# LEDMatrixLearningBadge.net
KiCad netlist of a schematic drawn in EAGLE
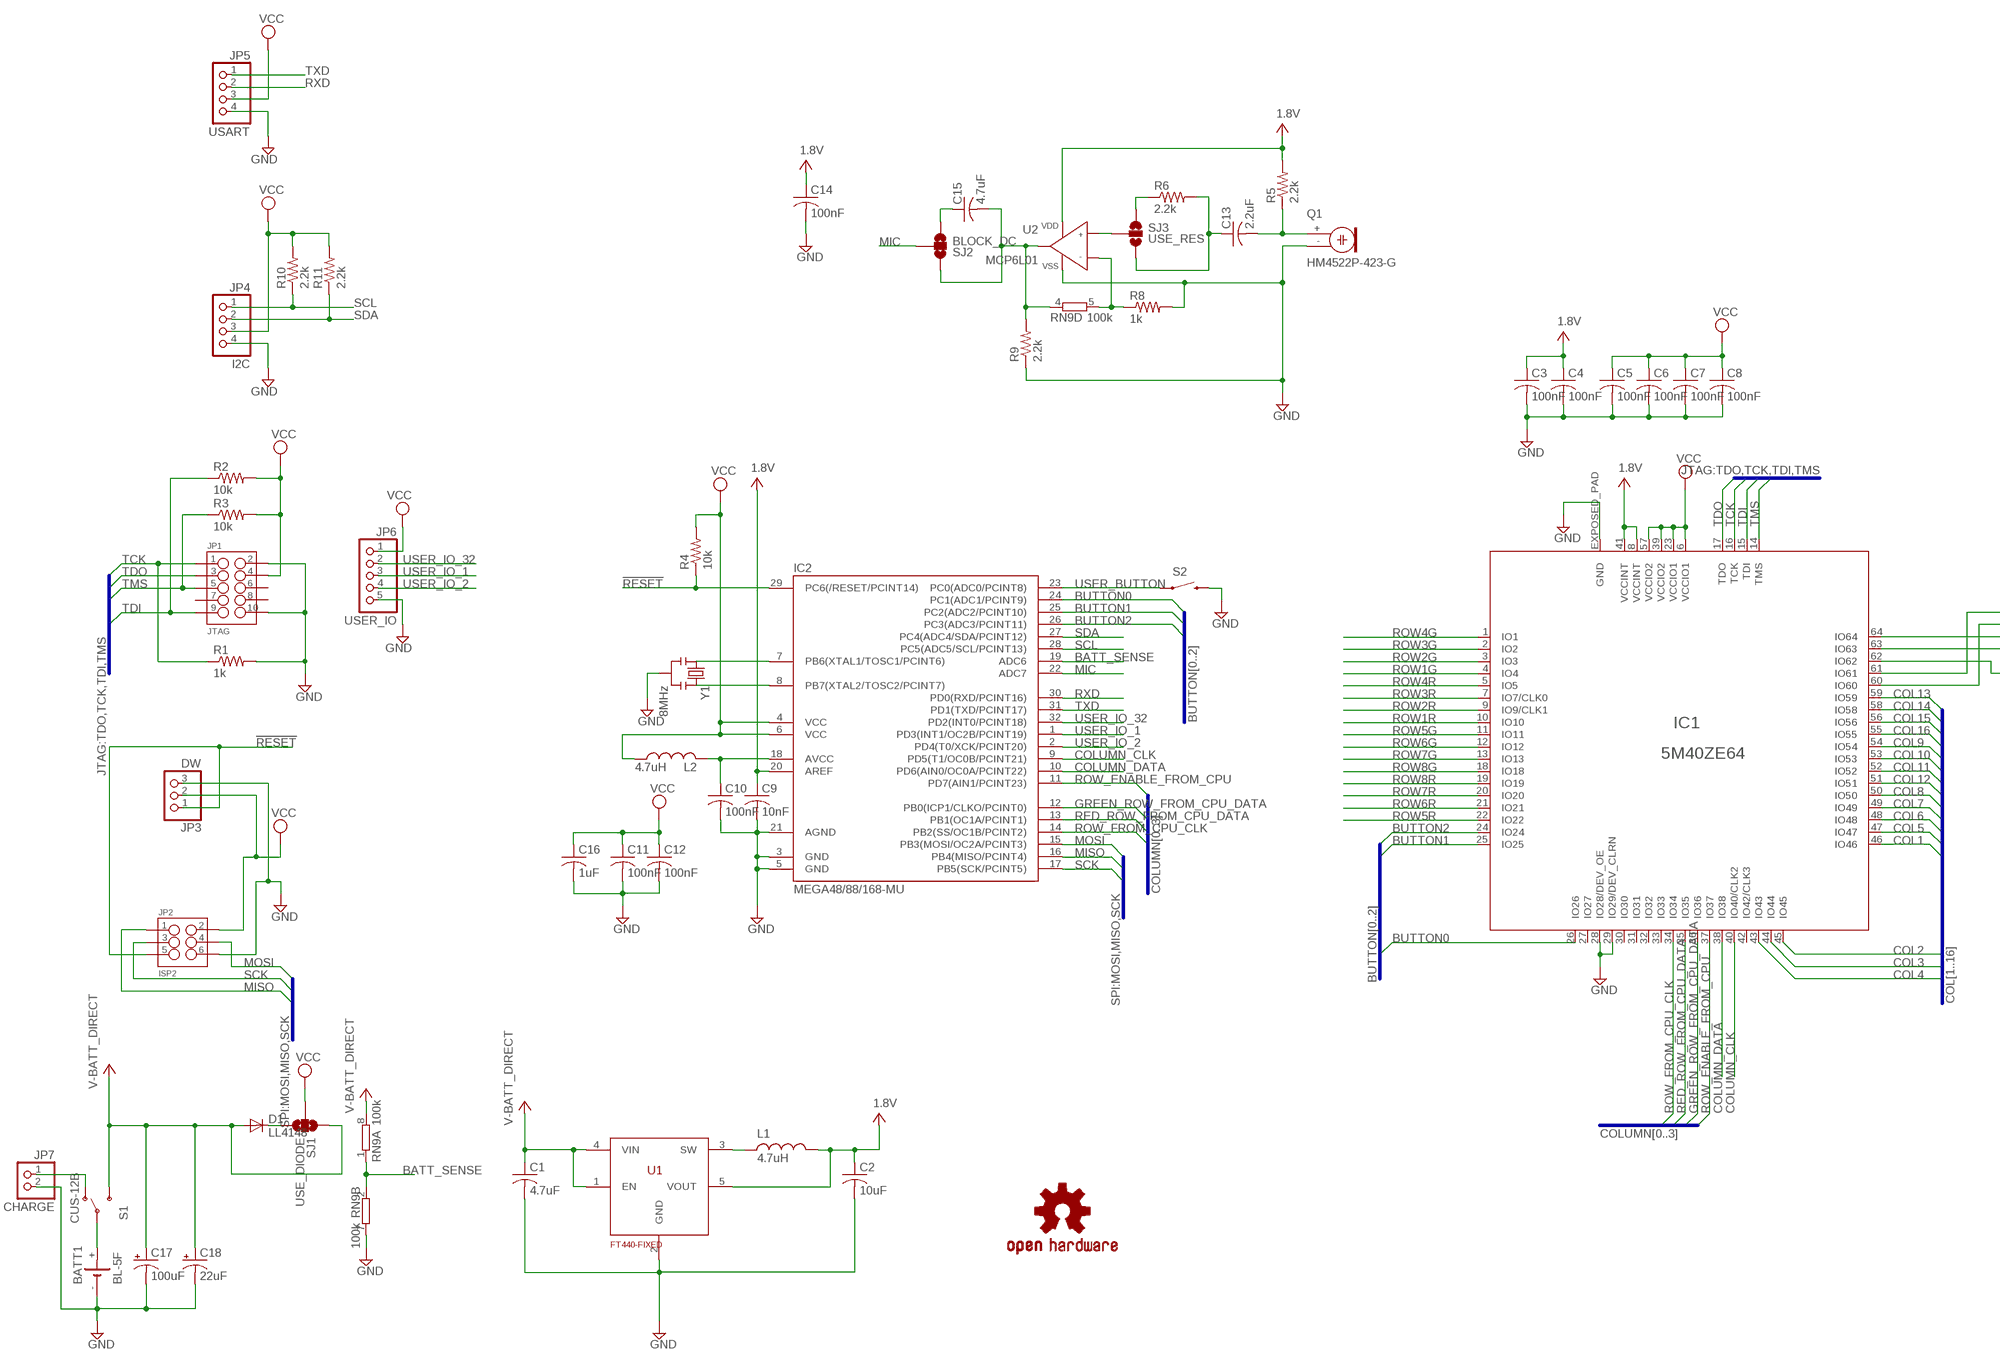
[diagram p0: schematic, sheet 1, part 1 of 2]
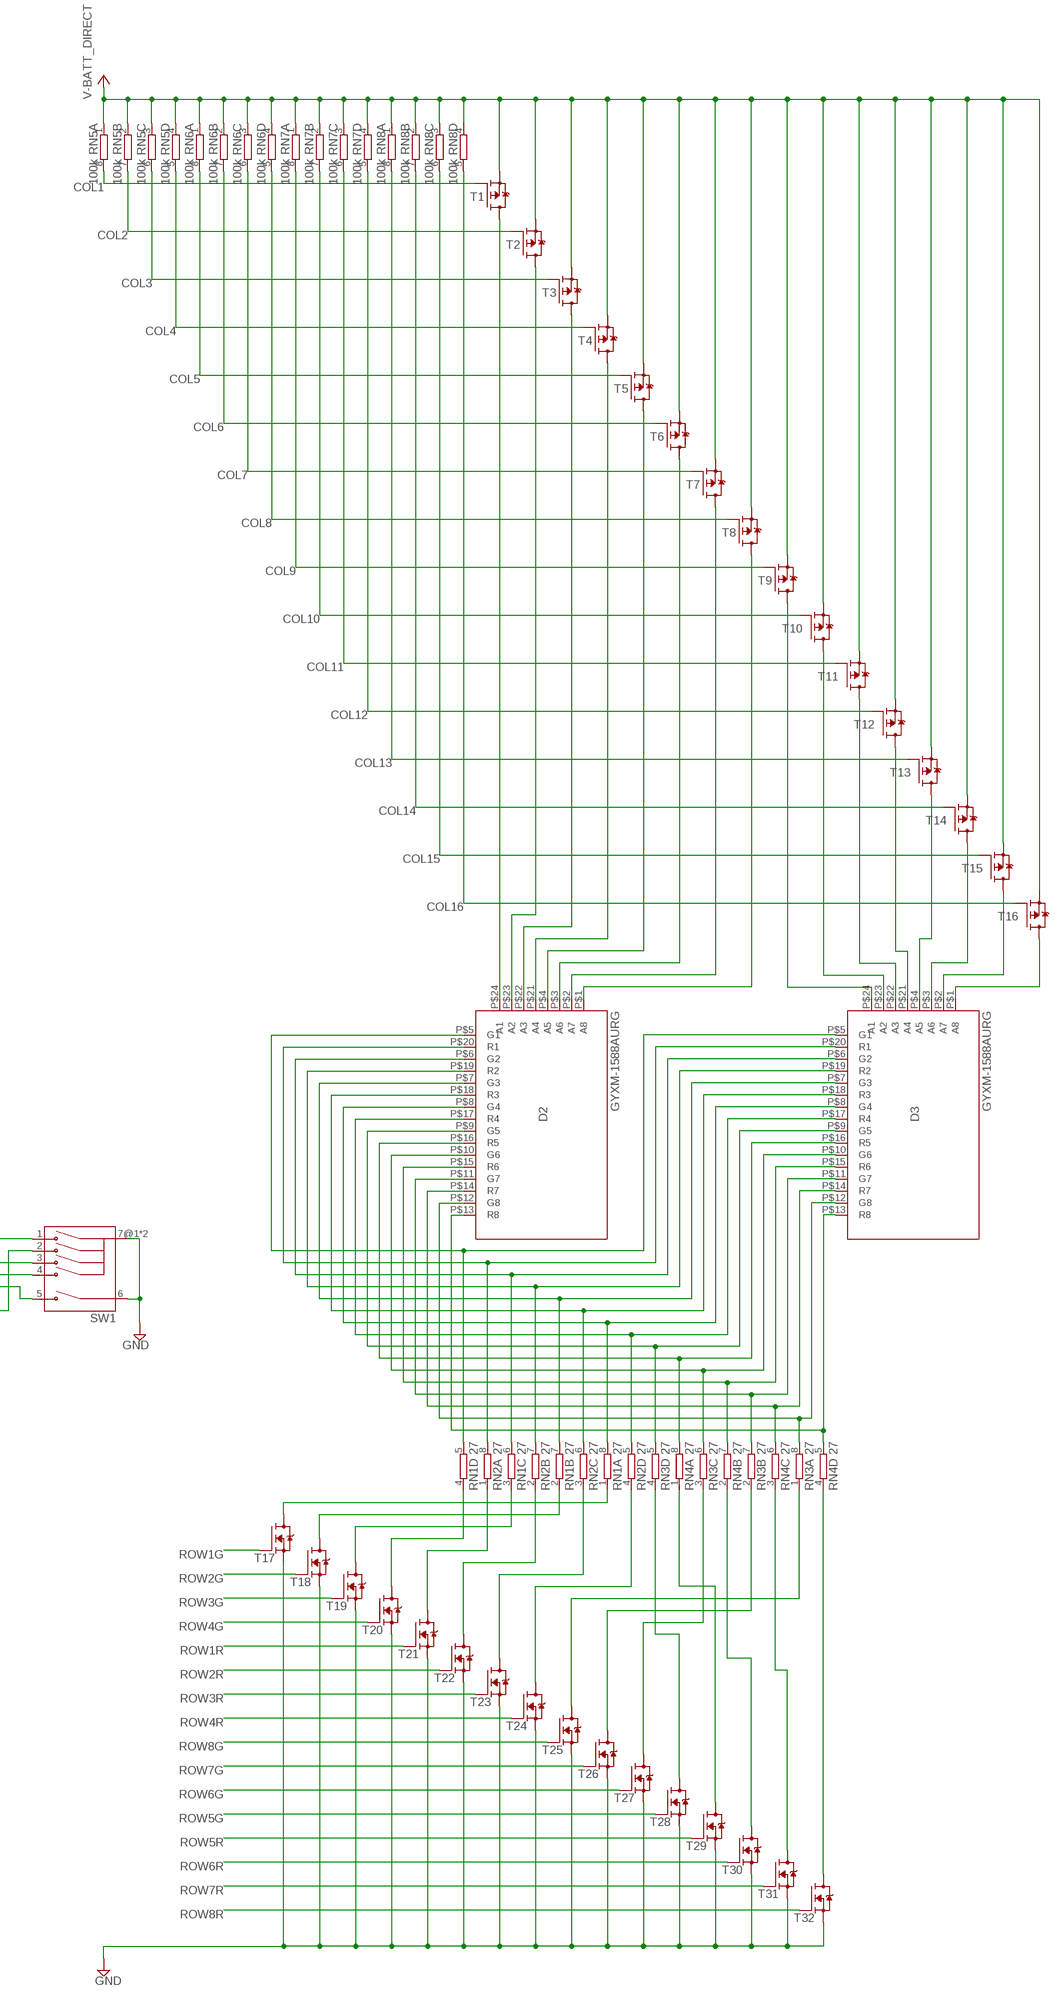
[diagram p1: schematic, sheet 1, part 2 of 2]

(export (version "E")
  (design (tool "Eeschema 10.0.6"))
  (components
    (comp (ref "BATT1")
      (value "BL-5F")
      (footprint "eagle-import:NOKIA_BL-5F_INCL_HOLDER")
      (libsource (lib "eagle-import") (part "1C"))
    )
    (comp (ref "C1")
      (value "4.7uF")
      (footprint "eagle-import:C0603")
      (libsource (lib "eagle-import") (part "C-USC0603"))
    )
    (comp (ref "C2")
      (value "10uF")
      (footprint "eagle-import:C0508")
      (libsource (lib "eagle-import") (part "C0508"))
    )
    (comp (ref "C3")
      (value "100nF")
      (footprint "eagle-import:C0603")
      (libsource (lib "eagle-import") (part "C-USC0603"))
    )
    (comp (ref "C4")
      (value "100nF")
      (footprint "eagle-import:C0603")
      (libsource (lib "eagle-import") (part "C-USC0603"))
    )
    (comp (ref "C5")
      (value "100nF")
      (footprint "eagle-import:C0603")
      (libsource (lib "eagle-import") (part "C-USC0603"))
    )
    (comp (ref "C6")
      (value "100nF")
      (footprint "eagle-import:C0603")
      (libsource (lib "eagle-import") (part "C-USC0603"))
    )
    (comp (ref "C7")
      (value "100nF")
      (footprint "eagle-import:C0603")
      (libsource (lib "eagle-import") (part "C-USC0603"))
    )
    (comp (ref "C8")
      (value "100nF")
      (footprint "eagle-import:C0603")
      (libsource (lib "eagle-import") (part "C-USC0603"))
    )
    (comp (ref "C9")
      (value "10nF")
      (footprint "eagle-import:C0603")
      (libsource (lib "eagle-import") (part "C-USC0603"))
    )
    (comp (ref "C10")
      (value "100nF")
      (footprint "eagle-import:C0603")
      (libsource (lib "eagle-import") (part "C-USC0603"))
    )
    (comp (ref "C11")
      (value "100nF")
      (footprint "eagle-import:C0603")
      (libsource (lib "eagle-import") (part "C-USC0603"))
    )
    (comp (ref "C12")
      (value "100nF")
      (footprint "eagle-import:C0603")
      (libsource (lib "eagle-import") (part "C-USC0603"))
    )
    (comp (ref "C13")
      (value "2.2uF")
      (footprint "eagle-import:C0603")
      (libsource (lib "eagle-import") (part "C-USC0603"))
    )
    (comp (ref "C14")
      (value "100nF")
      (footprint "eagle-import:C0603")
      (libsource (lib "eagle-import") (part "C-USC0603"))
    )
    (comp (ref "C15")
      (value "4.7uF")
      (footprint "eagle-import:C0603")
      (libsource (lib "eagle-import") (part "C-USC0603"))
    )
    (comp (ref "C16")
      (value "1uF")
      (footprint "eagle-import:C0603")
      (libsource (lib "eagle-import") (part "C-USC0603"))
    )
    (comp (ref "C17")
      (value "100uF")
      (footprint "eagle-import:C_6032-28R")
      (libsource (lib "eagle-import") (part "CPOL-USC/6032-28R"))
    )
    (comp (ref "C18")
      (value "22uF")
      (footprint "eagle-import:D_7343-31R")
      (libsource (lib "eagle-import") (part "CPOL-USD/7343-31R"))
    )
    (comp (ref "D1")
      (value "LL4148")
      (footprint "eagle-import:SOD80C")
      (libsource (lib "eagle-import") (part "DIODE-SOD80C"))
    )
    (comp (ref "D2")
      (value "GYXM-1588AURG")
      (footprint "eagle-import:GYXM-1588AURG")
      (libsource (lib "eagle-import") (part "GYXM-1588AURG"))
    )
    (comp (ref "D3")
      (value "GYXM-1588AURG")
      (footprint "eagle-import:GYXM-1588AURG")
      (libsource (lib "eagle-import") (part "GYXM-1588AURG"))
    )
    (comp (ref "IC1")
      (value "5M40ZE64")
      (footprint "eagle-import:EQFP64")
      (libsource (lib "eagle-import") (part "5M40ZE64"))
    )
    (comp (ref "IC2")
      (value "MEGA48/88/168-MU")
      (footprint "eagle-import:MLF32")
      (libsource (lib "eagle-import") (part "MEGA48/88/168-MU"))
    )
    (comp (ref "JP1")
      (value "JTAG")
      (footprint "eagle-import:2X5_POGO")
      (libsource (lib "eagle-import") (part "M05X2"))
    )
    (comp (ref "JP2")
      (value "ISP2")
      (footprint "eagle-import:2X3_POGO")
      (libsource (lib "eagle-import") (part "M03X2POGO_PINS"))
    )
    (comp (ref "JP3")
      (value "DW")
      (footprint "eagle-import:1X03")
      (libsource (lib "eagle-import") (part "PINHD-1X3"))
    )
    (comp (ref "JP4")
      (value "I2C")
      (footprint "eagle-import:1X04")
      (libsource (lib "eagle-import") (part "PINHD-1X4"))
    )
    (comp (ref "JP5")
      (value "USART")
      (footprint "eagle-import:1X04")
      (libsource (lib "eagle-import") (part "PINHD-1X4"))
    )
    (comp (ref "JP6")
      (value "USER_IO")
      (footprint "eagle-import:1X05")
      (libsource (lib "eagle-import") (part "PINHD-1X5"))
    )
    (comp (ref "JP7")
      (value "CHARGE")
      (footprint "eagle-import:1X02")
      (libsource (lib "eagle-import") (part "PINHD-1X2"))
    )
    (comp (ref "L1")
      (value "4.7uH")
      (footprint "eagle-import:0603")
      (libsource (lib "eagle-import") (part "INDUCTOR0603"))
    )
    (comp (ref "L2")
      (value "4.7uH")
      (footprint "eagle-import:0603")
      (libsource (lib "eagle-import") (part "INDUCTOR0603"))
    )
    (comp (ref "LOGO1")
      (value "OSHW-LOGOS")
      (footprint "eagle-import:OSHW-LOGO-S")
      (libsource (lib "eagle-import") (part "OSHW-LOGOS"))
    )
    (comp (ref "Q1")
      (value "HM4522P-423-G")
      (footprint "eagle-import:4.5ELECTRET")
      (libsource (lib "eagle-import") (part "ELECTRET4.5MM"))
    )
    (comp (ref "R1")
      (value "1k")
      (footprint "eagle-import:R0603")
      (libsource (lib "eagle-import") (part "R-US_R0603"))
    )
    (comp (ref "R2")
      (value "10k")
      (footprint "eagle-import:R0603")
      (libsource (lib "eagle-import") (part "R-US_R0603"))
    )
    (comp (ref "R3")
      (value "10k")
      (footprint "eagle-import:R0603")
      (libsource (lib "eagle-import") (part "R-US_R0603"))
    )
    (comp (ref "R4")
      (value "10k")
      (footprint "eagle-import:R0603")
      (libsource (lib "eagle-import") (part "R-US_R0603"))
    )
    (comp (ref "R5")
      (value "2.2k")
      (footprint "eagle-import:R0603")
      (libsource (lib "eagle-import") (part "R-US_R0603"))
    )
    (comp (ref "R6")
      (value "2.2k")
      (footprint "eagle-import:R0603")
      (libsource (lib "eagle-import") (part "R-US_R0603"))
    )
    (comp (ref "R8")
      (value "1k")
      (footprint "eagle-import:R0603")
      (libsource (lib "eagle-import") (part "R-US_R0603"))
    )
    (comp (ref "R9")
      (value "2.2k")
      (footprint "eagle-import:R0603")
      (libsource (lib "eagle-import") (part "R-US_R0603"))
    )
    (comp (ref "R10")
      (value "2.2k")
      (footprint "eagle-import:R0603")
      (libsource (lib "eagle-import") (part "R-US_R0603"))
    )
    (comp (ref "R11")
      (value "2.2k")
      (footprint "eagle-import:R0603")
      (libsource (lib "eagle-import") (part "R-US_R0603"))
    )
    (comp (ref "RN1")
      (value "27")
      (footprint "eagle-import:0603-ARV")
      (libsource (lib "eagle-import") (part "4R-N0603-ARV"))
    )
    (comp (ref "RN2")
      (value "27")
      (footprint "eagle-import:0603-ARV")
      (libsource (lib "eagle-import") (part "4R-N0603-ARV"))
    )
    (comp (ref "RN3")
      (value "27")
      (footprint "eagle-import:0603-ARV")
      (libsource (lib "eagle-import") (part "4R-N0603-ARV"))
    )
    (comp (ref "RN4")
      (value "27")
      (footprint "eagle-import:0603-ARV")
      (libsource (lib "eagle-import") (part "4R-N0603-ARV"))
    )
    (comp (ref "RN5")
      (value "100k")
      (footprint "eagle-import:0603-ARV")
      (libsource (lib "eagle-import") (part "4R-N0603-ARV"))
    )
    (comp (ref "RN6")
      (value "100k")
      (footprint "eagle-import:0603-ARV")
      (libsource (lib "eagle-import") (part "4R-N0603-ARV"))
    )
    (comp (ref "RN7")
      (value "100k")
      (footprint "eagle-import:0603-ARV")
      (libsource (lib "eagle-import") (part "4R-N0603-ARV"))
    )
    (comp (ref "RN8")
      (value "100k")
      (footprint "eagle-import:0603-ARV")
      (libsource (lib "eagle-import") (part "4R-N0603-ARV"))
    )
    (comp (ref "RN9")
      (value "100k")
      (footprint "eagle-import:0603-ARV")
      (libsource (lib "eagle-import") (part "4R-N0603-ARV"))
    )
    (comp (ref "S1")
      (value "CUS-12B")
      (footprint "eagle-import:SWITCH-SPST-SMD-A")
      (libsource (lib "eagle-import") (part "SWITCH-SPDT-SMD-A"))
    )
    (comp (ref "S2")
      (value "SWITCH-MOMENTARY-212MM")
      (footprint "eagle-import:TACTILE-PTH-12MM")
      (libsource (lib "eagle-import") (part "SWITCH-MOMENTARY-212MM"))
    )
    (comp (ref "SJ1")
      (value "USE_DIODE")
      (footprint "eagle-import:SJ_3_PASTE1&2")
      (libsource (lib "eagle-import") (part "SOLDERJUMPER_2WAYPASTE1&2"))
    )
    (comp (ref "SJ2")
      (value "BLOCK_DC")
      (footprint "eagle-import:SJ_3_PASTE1&2")
      (libsource (lib "eagle-import") (part "SOLDERJUMPER_2WAYPASTE1&2"))
    )
    (comp (ref "SJ3")
      (value "USE_RES")
      (footprint "eagle-import:SJ_3_PASTE1&2")
      (libsource (lib "eagle-import") (part "SOLDERJUMPER_2WAYPASTE1&2"))
    )
    (comp (ref "SW1")
      (value "4_DIRECTIONAL_JOYSTICK_PLUS_CENTER")
      (footprint "eagle-import:EVQWH")
      (libsource (lib "eagle-import") (part "4_DIRECTIONAL_JOYSTICK_PLUS_CENTER"))
    )
    (comp (ref "T1")
      (value "ZXM61P03")
      (footprint "eagle-import:SOT23")
      (libsource (lib "eagle-import") (part "P-MOSFET"))
    )
    (comp (ref "T2")
      (value "ZXM61P03")
      (footprint "eagle-import:SOT23")
      (libsource (lib "eagle-import") (part "P-MOSFET"))
    )
    (comp (ref "T3")
      (value "ZXM61P03")
      (footprint "eagle-import:SOT23")
      (libsource (lib "eagle-import") (part "P-MOSFET"))
    )
    (comp (ref "T4")
      (value "ZXM61P03")
      (footprint "eagle-import:SOT23")
      (libsource (lib "eagle-import") (part "P-MOSFET"))
    )
    (comp (ref "T5")
      (value "ZXM61P03")
      (footprint "eagle-import:SOT23")
      (libsource (lib "eagle-import") (part "P-MOSFET"))
    )
    (comp (ref "T6")
      (value "ZXM61P03")
      (footprint "eagle-import:SOT23")
      (libsource (lib "eagle-import") (part "P-MOSFET"))
    )
    (comp (ref "T7")
      (value "ZXM61P03")
      (footprint "eagle-import:SOT23")
      (libsource (lib "eagle-import") (part "P-MOSFET"))
    )
    (comp (ref "T8")
      (value "ZXM61P03")
      (footprint "eagle-import:SOT23")
      (libsource (lib "eagle-import") (part "P-MOSFET"))
    )
    (comp (ref "T9")
      (value "ZXM61P03")
      (footprint "eagle-import:SOT23")
      (libsource (lib "eagle-import") (part "P-MOSFET"))
    )
    (comp (ref "T10")
      (value "ZXM61P03")
      (footprint "eagle-import:SOT23")
      (libsource (lib "eagle-import") (part "P-MOSFET"))
    )
    (comp (ref "T11")
      (value "ZXM61P03")
      (footprint "eagle-import:SOT23")
      (libsource (lib "eagle-import") (part "P-MOSFET"))
    )
    (comp (ref "T12")
      (value "ZXM61P03")
      (footprint "eagle-import:SOT23")
      (libsource (lib "eagle-import") (part "P-MOSFET"))
    )
    (comp (ref "T13")
      (value "ZXM61P03")
      (footprint "eagle-import:SOT23")
      (libsource (lib "eagle-import") (part "P-MOSFET"))
    )
    (comp (ref "T14")
      (value "ZXM61P03")
      (footprint "eagle-import:SOT23")
      (libsource (lib "eagle-import") (part "P-MOSFET"))
    )
    (comp (ref "T15")
      (value "ZXM61P03")
      (footprint "eagle-import:SOT23")
      (libsource (lib "eagle-import") (part "P-MOSFET"))
    )
    (comp (ref "T16")
      (value "ZXM61P03")
      (footprint "eagle-import:SOT23")
      (libsource (lib "eagle-import") (part "P-MOSFET"))
    )
    (comp (ref "T17")
      (value "DMN65D8L")
      (footprint "eagle-import:SOT23")
      (libsource (lib "eagle-import") (part "N-MOSFET"))
    )
    (comp (ref "T18")
      (value "DMN65D8L")
      (footprint "eagle-import:SOT23")
      (libsource (lib "eagle-import") (part "N-MOSFET"))
    )
    (comp (ref "T19")
      (value "DMN65D8L")
      (footprint "eagle-import:SOT23")
      (libsource (lib "eagle-import") (part "N-MOSFET"))
    )
    (comp (ref "T20")
      (value "DMN65D8L")
      (footprint "eagle-import:SOT23")
      (libsource (lib "eagle-import") (part "N-MOSFET"))
    )
    (comp (ref "T21")
      (value "DMN65D8L")
      (footprint "eagle-import:SOT23")
      (libsource (lib "eagle-import") (part "N-MOSFET"))
    )
    (comp (ref "T22")
      (value "DMN65D8L")
      (footprint "eagle-import:SOT23")
      (libsource (lib "eagle-import") (part "N-MOSFET"))
    )
    (comp (ref "T23")
      (value "DMN65D8L")
      (footprint "eagle-import:SOT23")
      (libsource (lib "eagle-import") (part "N-MOSFET"))
    )
    (comp (ref "T24")
      (value "DMN65D8L")
      (footprint "eagle-import:SOT23")
      (libsource (lib "eagle-import") (part "N-MOSFET"))
    )
    (comp (ref "T25")
      (value "DMN65D8L")
      (footprint "eagle-import:SOT23")
      (libsource (lib "eagle-import") (part "N-MOSFET"))
    )
    (comp (ref "T26")
      (value "DMN65D8L")
      (footprint "eagle-import:SOT23")
      (libsource (lib "eagle-import") (part "N-MOSFET"))
    )
    (comp (ref "T27")
      (value "DMN65D8L")
      (footprint "eagle-import:SOT23")
      (libsource (lib "eagle-import") (part "N-MOSFET"))
    )
    (comp (ref "T28")
      (value "DMN65D8L")
      (footprint "eagle-import:SOT23")
      (libsource (lib "eagle-import") (part "N-MOSFET"))
    )
    (comp (ref "T29")
      (value "DMN65D8L")
      (footprint "eagle-import:SOT23")
      (libsource (lib "eagle-import") (part "N-MOSFET"))
    )
    (comp (ref "T30")
      (value "DMN65D8L")
      (footprint "eagle-import:SOT23")
      (libsource (lib "eagle-import") (part "N-MOSFET"))
    )
    (comp (ref "T31")
      (value "DMN65D8L")
      (footprint "eagle-import:SOT23")
      (libsource (lib "eagle-import") (part "N-MOSFET"))
    )
    (comp (ref "T32")
      (value "DMN65D8L")
      (footprint "eagle-import:SOT23")
      (libsource (lib "eagle-import") (part "N-MOSFET"))
    )
    (comp (ref "U1")
      (value "FT440-FIXED")
      (footprint "eagle-import:SOT23-5")
      (libsource (lib "eagle-import") (part "FT440-FIXED"))
    )
    (comp (ref "U2")
      (value "MCP6L01")
      (footprint "eagle-import:SOT23-5")
      (libsource (lib "eagle-import") (part "MCP6L01"))
    )
    (comp (ref "Y1")
      (value "8MHz")
      (footprint "eagle-import:RESONATOR-SMD")
      (libsource (lib "eagle-import") (part "RESONATOR"))
    )
  )
  (nets
    (net (code "7") (name "/BATT_SENSE") (class "Default")
      (node (ref "IC2") (pin "19") (pinfunction "ADC6_19") (pintype "passive"))
      (node (ref "RN9") (pin "1") (pinfunction "1_1") (pintype "passive"))
      (node (ref "RN9") (pin "2") (pinfunction "1_2") (pintype "passive"))
    )
    (net (code "8") (name "/BUTTON0") (class "Default")
      (node (ref "IC1") (pin "26") (pinfunction "IO26_26") (pintype "bidirectional"))
      (node (ref "IC2") (pin "24") (pinfunction "PC1(ADC1/PCINT9)_24") (pintype "bidirectional"))
    )
    (net (code "9") (name "/BUTTON1") (class "Default")
      (node (ref "IC1") (pin "25") (pinfunction "IO25_25") (pintype "bidirectional"))
      (node (ref "IC2") (pin "25") (pinfunction "PC2(ADC2/PCINT10)_25") (pintype "bidirectional"))
    )
    (net (code "10") (name "/BUTTON2") (class "Default")
      (node (ref "IC1") (pin "24") (pinfunction "IO24_24") (pintype "bidirectional"))
      (node (ref "IC2") (pin "26") (pinfunction "PC3(ADC3/PCINT11)_26") (pintype "bidirectional"))
    )
    (net (code "12") (name "/COL1") (class "Default")
      (node (ref "IC1") (pin "46") (pinfunction "IO46_46") (pintype "bidirectional"))
      (node (ref "RN5") (pin "8") (pinfunction "2_8") (pintype "passive"))
      (node (ref "T1") (pin "1") (pinfunction "G_1") (pintype "passive"))
    )
    (net (code "13") (name "/COL2") (class "Default")
      (node (ref "IC1") (pin "45") (pinfunction "IO45_45") (pintype "bidirectional"))
      (node (ref "RN5") (pin "7") (pinfunction "2_7") (pintype "passive"))
      (node (ref "T2") (pin "1") (pinfunction "G_1") (pintype "passive"))
    )
    (net (code "14") (name "/COL3") (class "Default")
      (node (ref "IC1") (pin "44") (pinfunction "IO44_44") (pintype "bidirectional"))
      (node (ref "RN5") (pin "6") (pinfunction "2_6") (pintype "passive"))
      (node (ref "T3") (pin "1") (pinfunction "G_1") (pintype "passive"))
    )
    (net (code "15") (name "/COL4") (class "Default")
      (node (ref "IC1") (pin "43") (pinfunction "IO43_43") (pintype "bidirectional"))
      (node (ref "RN5") (pin "5") (pinfunction "2_5") (pintype "passive"))
      (node (ref "T4") (pin "1") (pinfunction "G_1") (pintype "passive"))
    )
    (net (code "16") (name "/COL5") (class "Default")
      (node (ref "IC1") (pin "47") (pinfunction "IO47_47") (pintype "bidirectional"))
      (node (ref "RN6") (pin "8") (pinfunction "2_8") (pintype "passive"))
      (node (ref "T5") (pin "1") (pinfunction "G_1") (pintype "passive"))
    )
    (net (code "17") (name "/COL6") (class "Default")
      (node (ref "IC1") (pin "48") (pinfunction "IO48_48") (pintype "bidirectional"))
      (node (ref "RN6") (pin "7") (pinfunction "2_7") (pintype "passive"))
      (node (ref "T6") (pin "1") (pinfunction "G_1") (pintype "passive"))
    )
    (net (code "18") (name "/COL7") (class "Default")
      (node (ref "IC1") (pin "49") (pinfunction "IO49_49") (pintype "bidirectional"))
      (node (ref "RN6") (pin "6") (pinfunction "2_6") (pintype "passive"))
      (node (ref "T7") (pin "1") (pinfunction "G_1") (pintype "passive"))
    )
    (net (code "19") (name "/COL8") (class "Default")
      (node (ref "IC1") (pin "50") (pinfunction "IO50_50") (pintype "bidirectional"))
      (node (ref "RN6") (pin "5") (pinfunction "2_5") (pintype "passive"))
      (node (ref "T8") (pin "1") (pinfunction "G_1") (pintype "passive"))
    )
    (net (code "20") (name "/COL9") (class "Default")
      (node (ref "IC1") (pin "54") (pinfunction "IO54_54") (pintype "bidirectional"))
      (node (ref "RN7") (pin "8") (pinfunction "2_8") (pintype "passive"))
      (node (ref "T9") (pin "1") (pinfunction "G_1") (pintype "passive"))
    )
    (net (code "21") (name "/COL10") (class "Default")
      (node (ref "IC1") (pin "53") (pinfunction "IO53_53") (pintype "bidirectional"))
      (node (ref "RN7") (pin "7") (pinfunction "2_7") (pintype "passive"))
      (node (ref "T10") (pin "1") (pinfunction "G_1") (pintype "passive"))
    )
    (net (code "22") (name "/COL11") (class "Default")
      (node (ref "IC1") (pin "52") (pinfunction "IO52_52") (pintype "bidirectional"))
      (node (ref "RN7") (pin "6") (pinfunction "2_6") (pintype "passive"))
      (node (ref "T11") (pin "1") (pinfunction "G_1") (pintype "passive"))
    )
    (net (code "23") (name "/COL12") (class "Default")
      (node (ref "IC1") (pin "51") (pinfunction "IO51_51") (pintype "bidirectional"))
      (node (ref "RN7") (pin "5") (pinfunction "2_5") (pintype "passive"))
      (node (ref "T12") (pin "1") (pinfunction "G_1") (pintype "passive"))
    )
    (net (code "24") (name "/COL13") (class "Default")
      (node (ref "IC1") (pin "59") (pinfunction "IO59_59") (pintype "bidirectional"))
      (node (ref "RN8") (pin "8") (pinfunction "2_8") (pintype "passive"))
      (node (ref "T13") (pin "1") (pinfunction "G_1") (pintype "passive"))
    )
    (net (code "25") (name "/COL14") (class "Default")
      (node (ref "IC1") (pin "58") (pinfunction "IO58_58") (pintype "bidirectional"))
      (node (ref "RN8") (pin "7") (pinfunction "2_7") (pintype "passive"))
      (node (ref "T14") (pin "1") (pinfunction "G_1") (pintype "passive"))
    )
    (net (code "26") (name "/COL15") (class "Default")
      (node (ref "IC1") (pin "56") (pinfunction "IO56_56") (pintype "bidirectional"))
      (node (ref "RN8") (pin "6") (pinfunction "2_6") (pintype "passive"))
      (node (ref "T15") (pin "1") (pinfunction "G_1") (pintype "passive"))
    )
    (net (code "27") (name "/COL16") (class "Default")
      (node (ref "IC1") (pin "55") (pinfunction "IO55_55") (pintype "bidirectional"))
      (node (ref "RN8") (pin "5") (pinfunction "2_5") (pintype "passive"))
      (node (ref "T16") (pin "1") (pinfunction "G_1") (pintype "passive"))
    )
    (net (code "29") (name "/COLUMN_CLK") (class "Default")
      (node (ref "IC1") (pin "40") (pinfunction "IO40/CLK2_40") (pintype "bidirectional"))
      (node (ref "IC2") (pin "9") (pinfunction "PD5(T1/OC0B/PCINT21)_9") (pintype "bidirectional"))
    )
    (net (code "30") (name "/COLUMN_DATA") (class "Default")
      (node (ref "IC1") (pin "38") (pinfunction "IO38_38") (pintype "bidirectional"))
      (node (ref "IC2") (pin "10") (pinfunction "PD6(AIN0/OC0A/PCINT22)_10") (pintype "bidirectional"))
    )
    (net (code "32") (name "/GREEN_ROW_FROM_CPU_DATA") (class "Default")
      (node (ref "IC1") (pin "36") (pinfunction "IO36_36") (pintype "bidirectional"))
      (node (ref "IC2") (pin "12") (pinfunction "PB0(ICP1/CLKO/PCINT0)_12") (pintype "bidirectional"))
    )
    (net (code "33") (name "/MIC") (class "Default")
      (node (ref "IC2") (pin "22") (pinfunction "ADC7_22") (pintype "passive"))
      (node (ref "SJ2") (pin "2") (pinfunction "2_2") (pintype "passive"))
    )
    (net (code "34") (name "/MISO") (class "Default")
      (node (ref "IC2") (pin "16") (pinfunction "PB4(MISO/PCINT4)_16") (pintype "bidirectional"))
      (node (ref "JP2") (pin "P$1") (pinfunction "1_P$1") (pintype "bidirectional"))
    )
    (net (code "35") (name "/MOSI") (class "Default")
      (node (ref "IC2") (pin "15") (pinfunction "PB3(MOSI/OC2A/PCINT3)_15") (pintype "bidirectional"))
      (node (ref "JP2") (pin "P$4") (pinfunction "4_P$4") (pintype "bidirectional"))
    )
    (net (code "36") (name "/RED_ROW_FROM_CPU_DATA") (class "Default")
      (node (ref "IC1") (pin "35") (pinfunction "IO35_35") (pintype "bidirectional"))
      (node (ref "IC2") (pin "13") (pinfunction "PB1(OC1A/PCINT1)_13") (pintype "bidirectional"))
    )
    (net (code "37") (name "/ROW1G") (class "Default")
      (node (ref "IC1") (pin "4") (pinfunction "IO4_4") (pintype "bidirectional"))
      (node (ref "T17") (pin "1") (pinfunction "G_1") (pintype "passive"))
    )
    (net (code "38") (name "/ROW1R") (class "Default")
      (node (ref "IC1") (pin "10") (pinfunction "IO10_10") (pintype "bidirectional"))
      (node (ref "T21") (pin "1") (pinfunction "G_1") (pintype "passive"))
    )
    (net (code "39") (name "/ROW2G") (class "Default")
      (node (ref "IC1") (pin "3") (pinfunction "IO3_3") (pintype "bidirectional"))
      (node (ref "T18") (pin "1") (pinfunction "G_1") (pintype "passive"))
    )
    (net (code "40") (name "/ROW2R") (class "Default")
      (node (ref "IC1") (pin "9") (pinfunction "IO9/CLK1_9") (pintype "bidirectional"))
      (node (ref "T22") (pin "1") (pinfunction "G_1") (pintype "passive"))
    )
    (net (code "41") (name "/ROW3G") (class "Default")
      (node (ref "IC1") (pin "2") (pinfunction "IO2_2") (pintype "bidirectional"))
      (node (ref "T19") (pin "1") (pinfunction "G_1") (pintype "passive"))
    )
    (net (code "42") (name "/ROW3R") (class "Default")
      (node (ref "IC1") (pin "7") (pinfunction "IO7/CLK0_7") (pintype "bidirectional"))
      (node (ref "T23") (pin "1") (pinfunction "G_1") (pintype "passive"))
    )
    (net (code "43") (name "/ROW4G") (class "Default")
      (node (ref "IC1") (pin "1") (pinfunction "IO1_1") (pintype "bidirectional"))
      (node (ref "T20") (pin "1") (pinfunction "G_1") (pintype "passive"))
    )
    (net (code "44") (name "/ROW4R") (class "Default")
      (node (ref "IC1") (pin "5") (pinfunction "IO5_5") (pintype "bidirectional"))
      (node (ref "T24") (pin "1") (pinfunction "G_1") (pintype "passive"))
    )
    (net (code "45") (name "/ROW5G") (class "Default")
      (node (ref "IC1") (pin "11") (pinfunction "IO11_11") (pintype "bidirectional"))
      (node (ref "T28") (pin "1") (pinfunction "G_1") (pintype "passive"))
    )
    (net (code "46") (name "/ROW5R") (class "Default")
      (node (ref "IC1") (pin "22") (pinfunction "IO22_22") (pintype "bidirectional"))
      (node (ref "T29") (pin "1") (pinfunction "G_1") (pintype "passive"))
    )
    (net (code "47") (name "/ROW6G") (class "Default")
      (node (ref "IC1") (pin "12") (pinfunction "IO12_12") (pintype "bidirectional"))
      (node (ref "T27") (pin "1") (pinfunction "G_1") (pintype "passive"))
    )
    (net (code "48") (name "/ROW6R") (class "Default")
      (node (ref "IC1") (pin "21") (pinfunction "IO21_21") (pintype "bidirectional"))
      (node (ref "T30") (pin "1") (pinfunction "G_1") (pintype "passive"))
    )
    (net (code "49") (name "/ROW7G") (class "Default")
      (node (ref "IC1") (pin "13") (pinfunction "IO13_13") (pintype "bidirectional"))
      (node (ref "T26") (pin "1") (pinfunction "G_1") (pintype "passive"))
    )
    (net (code "50") (name "/ROW7R") (class "Default")
      (node (ref "IC1") (pin "20") (pinfunction "IO20_20") (pintype "bidirectional"))
      (node (ref "T31") (pin "1") (pinfunction "G_1") (pintype "passive"))
    )
    (net (code "51") (name "/ROW8G") (class "Default")
      (node (ref "IC1") (pin "18") (pinfunction "IO18_18") (pintype "bidirectional"))
      (node (ref "T25") (pin "1") (pinfunction "G_1") (pintype "passive"))
    )
    (net (code "52") (name "/ROW8R") (class "Default")
      (node (ref "IC1") (pin "19") (pinfunction "IO19_19") (pintype "bidirectional"))
      (node (ref "T32") (pin "1") (pinfunction "G_1") (pintype "passive"))
    )
    (net (code "53") (name "/ROW_ENABLE_FROM_CPU") (class "Default")
      (node (ref "IC1") (pin "37") (pinfunction "IO37_37") (pintype "bidirectional"))
      (node (ref "IC2") (pin "11") (pinfunction "PD7(AIN1/PCINT23)_11") (pintype "bidirectional"))
    )
    (net (code "54") (name "/ROW_FROM_CPU_CLK") (class "Default")
      (node (ref "IC1") (pin "34") (pinfunction "IO34_34") (pintype "bidirectional"))
      (node (ref "IC2") (pin "14") (pinfunction "PB2(SS/OC1B/PCINT2)_14") (pintype "bidirectional"))
    )
    (net (code "55") (name "/RXD") (class "Default")
      (node (ref "IC2") (pin "30") (pinfunction "PD0(RXD/PCINT16)_30") (pintype "bidirectional"))
      (node (ref "JP5") (pin "2") (pinfunction "2_2") (pintype "passive"))
    )
    (net (code "56") (name "/SCK") (class "Default")
      (node (ref "IC2") (pin "17") (pinfunction "PB5(SCK/PCINT5)_17") (pintype "bidirectional"))
      (node (ref "JP2") (pin "P$3") (pinfunction "3_P$3") (pintype "bidirectional"))
    )
    (net (code "57") (name "/SCL") (class "Default")
      (node (ref "IC2") (pin "28") (pinfunction "PC5(ADC5/SCL/PCINT13)_28") (pintype "bidirectional"))
      (node (ref "JP4") (pin "1") (pinfunction "1_1") (pintype "passive"))
      (node (ref "R10") (pin "1") (pinfunction "1_1") (pintype "passive"))
    )
    (net (code "58") (name "/SDA") (class "Default")
      (node (ref "IC2") (pin "27") (pinfunction "PC4(ADC4/SDA/PCINT12)_27") (pintype "bidirectional"))
      (node (ref "JP4") (pin "2") (pinfunction "2_2") (pintype "passive"))
      (node (ref "R11") (pin "1") (pinfunction "1_1") (pintype "passive"))
    )
    (net (code "59") (name "/TCK") (class "Default")
      (node (ref "IC1") (pin "16") (pinfunction "TCK_16") (pintype "input"))
      (node (ref "JP1") (pin "P$1") (pinfunction "1_P$1") (pintype "bidirectional"))
      (node (ref "R1") (pin "1") (pinfunction "1_1") (pintype "passive"))
    )
    (net (code "60") (name "/TDI") (class "Default")
      (node (ref "IC1") (pin "15") (pinfunction "TDI_15") (pintype "input"))
      (node (ref "JP1") (pin "P$9") (pinfunction "9_P$9") (pintype "bidirectional"))
      (node (ref "R2") (pin "1") (pinfunction "1_1") (pintype "passive"))
    )
    (net (code "61") (name "/TDO") (class "Default")
      (node (ref "IC1") (pin "17") (pinfunction "TDO_17") (pintype "output"))
      (node (ref "JP1") (pin "P$3") (pinfunction "3_P$3") (pintype "bidirectional"))
    )
    (net (code "62") (name "/TMS") (class "Default")
      (node (ref "IC1") (pin "14") (pinfunction "TMS_14") (pintype "input"))
      (node (ref "JP1") (pin "P$5") (pinfunction "5_P$5") (pintype "bidirectional"))
      (node (ref "R3") (pin "1") (pinfunction "1_1") (pintype "passive"))
    )
    (net (code "63") (name "/TXD") (class "Default")
      (node (ref "IC2") (pin "31") (pinfunction "PD1(TXD/PCINT17)_31") (pintype "bidirectional"))
      (node (ref "JP5") (pin "1") (pinfunction "1_1") (pintype "passive"))
    )
    (net (code "64") (name "/USER_BUTTON") (class "Default")
      (node (ref "IC2") (pin "23") (pinfunction "PC0(ADC0/PCINT8)_23") (pintype "bidirectional"))
      (node (ref "S2") (pin "1") (pinfunction "1_1") (pintype "passive"))
    )
    (net (code "65") (name "/USER_IO_1") (class "Default")
      (node (ref "IC2") (pin "1") (pinfunction "PD3(INT1/OC2B/PCINT19)_1") (pintype "bidirectional"))
      (node (ref "JP6") (pin "3") (pinfunction "3_3") (pintype "passive"))
    )
    (net (code "66") (name "/USER_IO_2") (class "Default")
      (node (ref "IC2") (pin "2") (pinfunction "PD4(T0/XCK/PCINT20)_2") (pintype "bidirectional"))
      (node (ref "JP6") (pin "4") (pinfunction "4_4") (pintype "passive"))
    )
    (net (code "67") (name "/USER_IO_32") (class "Default")
      (node (ref "IC2") (pin "32") (pinfunction "PD2(INT0/PCINT18)_32") (pintype "bidirectional"))
      (node (ref "JP6") (pin "2") (pinfunction "2_2") (pintype "passive"))
    )
    (net (code "70") (name "/~{RESET}") (class "Default")
      (node (ref "IC2") (pin "29") (pinfunction "PC6(/RESET/PCINT14)_29") (pintype "bidirectional"))
      (node (ref "JP2") (pin "P$5") (pinfunction "5_P$5") (pintype "bidirectional"))
      (node (ref "JP3") (pin "1") (pinfunction "1_1") (pintype "passive"))
      (node (ref "R4") (pin "1") (pinfunction "1_1") (pintype "passive"))
    )
    (net (code "71") (name "1.8V") (class "Default")
      (node (ref "C14") (pin "1") (pinfunction "1_1") (pintype "passive"))
      (node (ref "C2") (pin "P$1") (pinfunction "1_P$1") (pintype "passive"))
      (node (ref "C3") (pin "1") (pinfunction "1_1") (pintype "passive"))
      (node (ref "C4") (pin "1") (pinfunction "1_1") (pintype "passive"))
      (node (ref "C9") (pin "1") (pinfunction "1_1") (pintype "passive"))
      (node (ref "IC1") (pin "41") (pinfunction "VCCINT_41") (pintype "power_in"))
      (node (ref "IC1") (pin "8") (pinfunction "VCCINT_8") (pintype "power_in"))
      (node (ref "IC2") (pin "20") (pinfunction "AREF_20") (pintype "passive"))
      (node (ref "L1") (pin "2") (pinfunction "2_2") (pintype "passive"))
      (node (ref "R5") (pin "2") (pinfunction "2_2") (pintype "passive"))
      (node (ref "U1") (pin "5") (pinfunction "VOUT_5") (pintype "power_in"))
      (node (ref "U2") (pin "P5") (pinfunction "VDD_P5") (pintype "power_in"))
    )
    (net (code "72") (name "GND") (class "Default")
      (node (ref "BATT1") (pin "-") (pinfunction "-_-") (pintype "power_in"))
      (node (ref "C1") (pin "2") (pinfunction "2_2") (pintype "passive"))
      (node (ref "C10") (pin "2") (pinfunction "2_2") (pintype "passive"))
      (node (ref "C11") (pin "2") (pinfunction "2_2") (pintype "passive"))
      (node (ref "C12") (pin "2") (pinfunction "2_2") (pintype "passive"))
      (node (ref "C14") (pin "2") (pinfunction "2_2") (pintype "passive"))
      (node (ref "C16") (pin "2") (pinfunction "2_2") (pintype "passive"))
      (node (ref "C17") (pin "-") (pinfunction "-_-") (pintype "passive"))
      (node (ref "C18") (pin "-") (pinfunction "-_-") (pintype "passive"))
      (node (ref "C2") (pin "P$2") (pinfunction "2_P$2") (pintype "passive"))
      (node (ref "C3") (pin "2") (pinfunction "2_2") (pintype "passive"))
      (node (ref "C4") (pin "2") (pinfunction "2_2") (pintype "passive"))
      (node (ref "C5") (pin "2") (pinfunction "2_2") (pintype "passive"))
      (node (ref "C6") (pin "2") (pinfunction "2_2") (pintype "passive"))
      (node (ref "C7") (pin "2") (pinfunction "2_2") (pintype "passive"))
      (node (ref "C8") (pin "2") (pinfunction "2_2") (pintype "passive"))
      (node (ref "C9") (pin "2") (pinfunction "2_2") (pintype "passive"))
      (node (ref "IC1") (pin "28") (pinfunction "IO28/DEV_OE_28") (pintype "bidirectional"))
      (node (ref "IC1") (pin "29") (pinfunction "IO29/DEV_CLRN_29") (pintype "bidirectional"))
      (node (ref "IC1") (pin "EXPOSED_PAD") (pinfunction "GND_EXPOSED_PAD") (pintype "power_in"))
      (node (ref "IC2") (pin "21") (pinfunction "AGND_21") (pintype "power_in"))
      (node (ref "IC2") (pin "3") (pinfunction "GND_3") (pintype "power_in"))
      (node (ref "IC2") (pin "5") (pinfunction "GND_5") (pintype "power_in"))
      (node (ref "JP1") (pin "P$10") (pinfunction "10_P$10") (pintype "bidirectional"))
      (node (ref "JP1") (pin "P$2") (pinfunction "2_P$2") (pintype "bidirectional"))
      (node (ref "JP2") (pin "P$6") (pinfunction "6_P$6") (pintype "bidirectional"))
      (node (ref "JP3") (pin "3") (pinfunction "3_3") (pintype "passive"))
      (node (ref "JP4") (pin "4") (pinfunction "4_4") (pintype "passive"))
      (node (ref "JP5") (pin "4") (pinfunction "4_4") (pintype "passive"))
      (node (ref "JP6") (pin "5") (pinfunction "5_5") (pintype "passive"))
      (node (ref "JP7") (pin "2") (pinfunction "2_2") (pintype "passive"))
      (node (ref "Q1") (pin "-") (pinfunction "1_-") (pintype "passive"))
      (node (ref "R1") (pin "2") (pinfunction "2_2") (pintype "passive"))
      (node (ref "R8") (pin "2") (pinfunction "2_2") (pintype "passive"))
      (node (ref "R9") (pin "1") (pinfunction "1_1") (pintype "passive"))
      (node (ref "RN9") (pin "7") (pinfunction "2_7") (pintype "passive"))
      (node (ref "S2") (pin "3") (pinfunction "2_3") (pintype "passive"))
      (node (ref "SW1") (pin "6") (pinfunction "P$6_6") (pintype "passive"))
      (node (ref "SW1") (pin "7@1") (pinfunction "P$7_7@1") (pintype "passive"))
      (node (ref "SW1") (pin "7@2") (pinfunction "P$7_7@2") (pintype "passive"))
      (node (ref "T17") (pin "2") (pinfunction "S_2") (pintype "passive"))
      (node (ref "T18") (pin "2") (pinfunction "S_2") (pintype "passive"))
      (node (ref "T19") (pin "2") (pinfunction "S_2") (pintype "passive"))
      (node (ref "T20") (pin "2") (pinfunction "S_2") (pintype "passive"))
      (node (ref "T21") (pin "2") (pinfunction "S_2") (pintype "passive"))
      (node (ref "T22") (pin "2") (pinfunction "S_2") (pintype "passive"))
      (node (ref "T23") (pin "2") (pinfunction "S_2") (pintype "passive"))
      (node (ref "T24") (pin "2") (pinfunction "S_2") (pintype "passive"))
      (node (ref "T25") (pin "2") (pinfunction "S_2") (pintype "passive"))
      (node (ref "T26") (pin "2") (pinfunction "S_2") (pintype "passive"))
      (node (ref "T27") (pin "2") (pinfunction "S_2") (pintype "passive"))
      (node (ref "T28") (pin "2") (pinfunction "S_2") (pintype "passive"))
      (node (ref "T29") (pin "2") (pinfunction "S_2") (pintype "passive"))
      (node (ref "T30") (pin "2") (pinfunction "S_2") (pintype "passive"))
      (node (ref "T31") (pin "2") (pinfunction "S_2") (pintype "passive"))
      (node (ref "T32") (pin "2") (pinfunction "S_2") (pintype "passive"))
      (node (ref "U1") (pin "2") (pinfunction "GND_2") (pintype "power_in"))
      (node (ref "U2") (pin "P2") (pinfunction "VSS_P2") (pintype "power_in"))
      (node (ref "Y1") (pin "2") (pinfunction "2_2") (pintype "passive"))
    )
    (net (code "73") (name "Net-(C13-Pad1)") (class "Default")
      (node (ref "C13") (pin "1") (pinfunction "1_1") (pintype "passive"))
      (node (ref "R6") (pin "2") (pinfunction "2_2") (pintype "passive"))
      (node (ref "SJ3") (pin "3") (pinfunction "3_3") (pintype "passive"))
    )
    (net (code "74") (name "Net-(C15-Pad1)") (class "Default")
      (node (ref "C15") (pin "1") (pinfunction "1_1") (pintype "passive"))
      (node (ref "SJ2") (pin "3") (pinfunction "3_3") (pintype "passive"))
    )
    (net (code "75") (name "Net-(D1-PadC)") (class "Default")
      (node (ref "D1") (pin "C") (pinfunction "C_C") (pintype "passive"))
      (node (ref "SJ1") (pin "3") (pinfunction "3_3") (pintype "passive"))
    )
    (net (code "76") (name "Net-(D2-A1)") (class "Default")
      (node (ref "D2") (pin "P$24") (pinfunction "A1_P$24") (pintype "bidirectional"))
      (node (ref "T1") (pin "3") (pinfunction "D_3") (pintype "passive"))
    )
    (net (code "77") (name "Net-(D2-A2)") (class "Default")
      (node (ref "D2") (pin "P$23") (pinfunction "A2_P$23") (pintype "bidirectional"))
      (node (ref "T2") (pin "3") (pinfunction "D_3") (pintype "passive"))
    )
    (net (code "78") (name "Net-(D2-A3)") (class "Default")
      (node (ref "D2") (pin "P$22") (pinfunction "A3_P$22") (pintype "bidirectional"))
      (node (ref "T3") (pin "3") (pinfunction "D_3") (pintype "passive"))
    )
    (net (code "79") (name "Net-(D2-A4)") (class "Default")
      (node (ref "D2") (pin "P$21") (pinfunction "A4_P$21") (pintype "bidirectional"))
      (node (ref "T4") (pin "3") (pinfunction "D_3") (pintype "passive"))
    )
    (net (code "80") (name "Net-(D2-A5)") (class "Default")
      (node (ref "D2") (pin "P$4") (pinfunction "A5_P$4") (pintype "bidirectional"))
      (node (ref "T5") (pin "3") (pinfunction "D_3") (pintype "passive"))
    )
    (net (code "81") (name "Net-(D2-A6)") (class "Default")
      (node (ref "D2") (pin "P$3") (pinfunction "A6_P$3") (pintype "bidirectional"))
      (node (ref "T6") (pin "3") (pinfunction "D_3") (pintype "passive"))
    )
    (net (code "82") (name "Net-(D2-A7)") (class "Default")
      (node (ref "D2") (pin "P$2") (pinfunction "A7_P$2") (pintype "bidirectional"))
      (node (ref "T7") (pin "3") (pinfunction "D_3") (pintype "passive"))
    )
    (net (code "83") (name "Net-(D2-A8)") (class "Default")
      (node (ref "D2") (pin "P$1") (pinfunction "A8_P$1") (pintype "bidirectional"))
      (node (ref "T8") (pin "3") (pinfunction "D_3") (pintype "passive"))
    )
    (net (code "84") (name "Net-(D2-G1)") (class "Default")
      (node (ref "D2") (pin "P$5") (pinfunction "G1_P$5") (pintype "bidirectional"))
      (node (ref "D3") (pin "P$5") (pinfunction "G1_P$5") (pintype "bidirectional"))
      (node (ref "RN1") (pin "5") (pinfunction "2_5") (pintype "passive"))
    )
    (net (code "85") (name "Net-(D2-G2)") (class "Default")
      (node (ref "D2") (pin "P$6") (pinfunction "G2_P$6") (pintype "bidirectional"))
      (node (ref "D3") (pin "P$6") (pinfunction "G2_P$6") (pintype "bidirectional"))
      (node (ref "RN1") (pin "6") (pinfunction "2_6") (pintype "passive"))
    )
    (net (code "86") (name "Net-(D2-G3)") (class "Default")
      (node (ref "D2") (pin "P$7") (pinfunction "G3_P$7") (pintype "bidirectional"))
      (node (ref "D3") (pin "P$7") (pinfunction "G3_P$7") (pintype "bidirectional"))
      (node (ref "RN1") (pin "7") (pinfunction "2_7") (pintype "passive"))
    )
    (net (code "87") (name "Net-(D2-G4)") (class "Default")
      (node (ref "D2") (pin "P$8") (pinfunction "G4_P$8") (pintype "bidirectional"))
      (node (ref "D3") (pin "P$8") (pinfunction "G4_P$8") (pintype "bidirectional"))
      (node (ref "RN1") (pin "8") (pinfunction "2_8") (pintype "passive"))
    )
    (net (code "88") (name "Net-(D2-G5)") (class "Default")
      (node (ref "D2") (pin "P$9") (pinfunction "G5_P$9") (pintype "bidirectional"))
      (node (ref "D3") (pin "P$9") (pinfunction "G5_P$9") (pintype "bidirectional"))
      (node (ref "RN3") (pin "5") (pinfunction "2_5") (pintype "passive"))
    )
    (net (code "89") (name "Net-(D2-G6)") (class "Default")
      (node (ref "D2") (pin "P$10") (pinfunction "G6_P$10") (pintype "bidirectional"))
      (node (ref "D3") (pin "P$10") (pinfunction "G6_P$10") (pintype "bidirectional"))
      (node (ref "RN3") (pin "6") (pinfunction "2_6") (pintype "passive"))
    )
    (net (code "90") (name "Net-(D2-G7)") (class "Default")
      (node (ref "D2") (pin "P$11") (pinfunction "G7_P$11") (pintype "bidirectional"))
      (node (ref "D3") (pin "P$11") (pinfunction "G7_P$11") (pintype "bidirectional"))
      (node (ref "RN3") (pin "7") (pinfunction "2_7") (pintype "passive"))
    )
    (net (code "91") (name "Net-(D2-G8)") (class "Default")
      (node (ref "D2") (pin "P$12") (pinfunction "G8_P$12") (pintype "bidirectional"))
      (node (ref "D3") (pin "P$12") (pinfunction "G8_P$12") (pintype "bidirectional"))
      (node (ref "RN3") (pin "8") (pinfunction "2_8") (pintype "passive"))
    )
    (net (code "92") (name "Net-(D2-R1)") (class "Default")
      (node (ref "D2") (pin "P$20") (pinfunction "R1_P$20") (pintype "bidirectional"))
      (node (ref "D3") (pin "P$20") (pinfunction "R1_P$20") (pintype "bidirectional"))
      (node (ref "RN2") (pin "8") (pinfunction "2_8") (pintype "passive"))
    )
    (net (code "93") (name "Net-(D2-R2)") (class "Default")
      (node (ref "D2") (pin "P$19") (pinfunction "R2_P$19") (pintype "bidirectional"))
      (node (ref "D3") (pin "P$19") (pinfunction "R2_P$19") (pintype "bidirectional"))
      (node (ref "RN2") (pin "7") (pinfunction "2_7") (pintype "passive"))
    )
    (net (code "94") (name "Net-(D2-R3)") (class "Default")
      (node (ref "D2") (pin "P$18") (pinfunction "R3_P$18") (pintype "bidirectional"))
      (node (ref "D3") (pin "P$18") (pinfunction "R3_P$18") (pintype "bidirectional"))
      (node (ref "RN2") (pin "6") (pinfunction "2_6") (pintype "passive"))
    )
    (net (code "95") (name "Net-(D2-R4)") (class "Default")
      (node (ref "D2") (pin "P$17") (pinfunction "R4_P$17") (pintype "bidirectional"))
      (node (ref "D3") (pin "P$17") (pinfunction "R4_P$17") (pintype "bidirectional"))
      (node (ref "RN2") (pin "5") (pinfunction "2_5") (pintype "passive"))
    )
    (net (code "96") (name "Net-(D2-R5)") (class "Default")
      (node (ref "D2") (pin "P$16") (pinfunction "R5_P$16") (pintype "bidirectional"))
      (node (ref "D3") (pin "P$16") (pinfunction "R5_P$16") (pintype "bidirectional"))
      (node (ref "RN4") (pin "8") (pinfunction "2_8") (pintype "passive"))
    )
    (net (code "97") (name "Net-(D2-R6)") (class "Default")
      (node (ref "D2") (pin "P$15") (pinfunction "R6_P$15") (pintype "bidirectional"))
      (node (ref "D3") (pin "P$15") (pinfunction "R6_P$15") (pintype "bidirectional"))
      (node (ref "RN4") (pin "7") (pinfunction "2_7") (pintype "passive"))
    )
    (net (code "98") (name "Net-(D2-R7)") (class "Default")
      (node (ref "D2") (pin "P$14") (pinfunction "R7_P$14") (pintype "bidirectional"))
      (node (ref "D3") (pin "P$14") (pinfunction "R7_P$14") (pintype "bidirectional"))
      (node (ref "RN4") (pin "6") (pinfunction "2_6") (pintype "passive"))
    )
    (net (code "99") (name "Net-(D2-R8)") (class "Default")
      (node (ref "D2") (pin "P$13") (pinfunction "R8_P$13") (pintype "bidirectional"))
      (node (ref "D3") (pin "P$13") (pinfunction "R8_P$13") (pintype "bidirectional"))
      (node (ref "RN4") (pin "5") (pinfunction "2_5") (pintype "passive"))
    )
    (net (code "100") (name "Net-(D3-A1)") (class "Default")
      (node (ref "D3") (pin "P$24") (pinfunction "A1_P$24") (pintype "bidirectional"))
      (node (ref "T9") (pin "3") (pinfunction "D_3") (pintype "passive"))
    )
    (net (code "101") (name "Net-(D3-A2)") (class "Default")
      (node (ref "D3") (pin "P$23") (pinfunction "A2_P$23") (pintype "bidirectional"))
      (node (ref "T10") (pin "3") (pinfunction "D_3") (pintype "passive"))
    )
    (net (code "102") (name "Net-(D3-A3)") (class "Default")
      (node (ref "D3") (pin "P$22") (pinfunction "A3_P$22") (pintype "bidirectional"))
      (node (ref "T11") (pin "3") (pinfunction "D_3") (pintype "passive"))
    )
    (net (code "103") (name "Net-(D3-A4)") (class "Default")
      (node (ref "D3") (pin "P$21") (pinfunction "A4_P$21") (pintype "bidirectional"))
      (node (ref "T12") (pin "3") (pinfunction "D_3") (pintype "passive"))
    )
    (net (code "104") (name "Net-(D3-A5)") (class "Default")
      (node (ref "D3") (pin "P$4") (pinfunction "A5_P$4") (pintype "bidirectional"))
      (node (ref "T13") (pin "3") (pinfunction "D_3") (pintype "passive"))
    )
    (net (code "105") (name "Net-(D3-A6)") (class "Default")
      (node (ref "D3") (pin "P$3") (pinfunction "A6_P$3") (pintype "bidirectional"))
      (node (ref "T14") (pin "3") (pinfunction "D_3") (pintype "passive"))
    )
    (net (code "106") (name "Net-(D3-A7)") (class "Default")
      (node (ref "D3") (pin "P$2") (pinfunction "A7_P$2") (pintype "bidirectional"))
      (node (ref "T15") (pin "3") (pinfunction "D_3") (pintype "passive"))
    )
    (net (code "107") (name "Net-(D3-A8)") (class "Default")
      (node (ref "D3") (pin "P$1") (pinfunction "A8_P$1") (pintype "bidirectional"))
      (node (ref "T16") (pin "3") (pinfunction "D_3") (pintype "passive"))
    )
    (net (code "108") (name "Net-(IC1-IO60)") (class "Default")
      (node (ref "IC1") (pin "60") (pinfunction "IO60_60") (pintype "bidirectional"))
      (node (ref "SW1") (pin "2") (pinfunction "P$2_2") (pintype "passive"))
    )
    (net (code "109") (name "Net-(IC1-IO61)") (class "Default")
      (node (ref "IC1") (pin "61") (pinfunction "IO61_61") (pintype "bidirectional"))
      (node (ref "SW1") (pin "1") (pinfunction "P$1_1") (pintype "passive"))
    )
    (net (code "110") (name "Net-(IC1-IO62)") (class "Default")
      (node (ref "IC1") (pin "62") (pinfunction "IO62_62") (pintype "bidirectional"))
      (node (ref "SW1") (pin "5") (pinfunction "P$5_5") (pintype "passive"))
    )
    (net (code "111") (name "Net-(IC1-IO63)") (class "Default")
      (node (ref "IC1") (pin "63") (pinfunction "IO63_63") (pintype "bidirectional"))
      (node (ref "SW1") (pin "4") (pinfunction "P$4_4") (pintype "passive"))
    )
    (net (code "112") (name "Net-(IC1-IO64)") (class "Default")
      (node (ref "IC1") (pin "64") (pinfunction "IO64_64") (pintype "bidirectional"))
      (node (ref "SW1") (pin "3") (pinfunction "P$3_3") (pintype "passive"))
    )
    (net (code "113") (name "Net-(IC2-AVCC)") (class "Default")
      (node (ref "C10") (pin "1") (pinfunction "1_1") (pintype "passive"))
      (node (ref "IC2") (pin "18") (pinfunction "AVCC_18") (pintype "passive"))
      (node (ref "L2") (pin "2") (pinfunction "2_2") (pintype "passive"))
    )
    (net (code "114") (name "Net-(IC2-PB6(XTAL1{slash}TOSC1{slash}PCINT6))") (class "Default")
      (node (ref "IC2") (pin "7") (pinfunction "PB6(XTAL1/TOSC1/PCINT6)_7") (pintype "bidirectional"))
      (node (ref "Y1") (pin "1") (pinfunction "1_1") (pintype "passive"))
    )
    (net (code "115") (name "Net-(IC2-PB7(XTAL2{slash}TOSC2{slash}PCINT7))") (class "Default")
      (node (ref "IC2") (pin "8") (pinfunction "PB7(XTAL2/TOSC2/PCINT7)_8") (pintype "bidirectional"))
      (node (ref "Y1") (pin "3") (pinfunction "3_3") (pintype "passive"))
    )
    (net (code "116") (name "Net-(Q1-2)") (class "Default")
      (node (ref "C13") (pin "2") (pinfunction "2_2") (pintype "passive"))
      (node (ref "Q1") (pin "+") (pinfunction "2_+") (pintype "passive"))
      (node (ref "R5") (pin "1") (pinfunction "1_1") (pintype "passive"))
    )
    (net (code "117") (name "Net-(R6-Pad1)") (class "Default")
      (node (ref "R6") (pin "1") (pinfunction "1_1") (pintype "passive"))
      (node (ref "SJ3") (pin "1") (pinfunction "1_1") (pintype "passive"))
    )
    (net (code "118") (name "Net-(RN1B-1)") (class "Default")
      (node (ref "RN1") (pin "2") (pinfunction "1_2") (pintype "passive"))
      (node (ref "T18") (pin "3") (pinfunction "D_3") (pintype "passive"))
    )
    (net (code "119") (name "Net-(RN1C-1)") (class "Default")
      (node (ref "RN1") (pin "3") (pinfunction "1_3") (pintype "passive"))
      (node (ref "T19") (pin "3") (pinfunction "D_3") (pintype "passive"))
    )
    (net (code "120") (name "Net-(RN1D-1)") (class "Default")
      (node (ref "RN1") (pin "4") (pinfunction "1_4") (pintype "passive"))
      (node (ref "T20") (pin "3") (pinfunction "D_3") (pintype "passive"))
    )
    (net (code "121") (name "Net-(RN2B-1)") (class "Default")
      (node (ref "RN2") (pin "2") (pinfunction "1_2") (pintype "passive"))
      (node (ref "T22") (pin "3") (pinfunction "D_3") (pintype "passive"))
    )
    (net (code "122") (name "Net-(RN2C-1)") (class "Default")
      (node (ref "RN2") (pin "3") (pinfunction "1_3") (pintype "passive"))
      (node (ref "T23") (pin "3") (pinfunction "D_3") (pintype "passive"))
    )
    (net (code "123") (name "Net-(RN2D-1)") (class "Default")
      (node (ref "RN2") (pin "4") (pinfunction "1_4") (pintype "passive"))
      (node (ref "T24") (pin "3") (pinfunction "D_3") (pintype "passive"))
    )
    (net (code "124") (name "Net-(RN3B-1)") (class "Default")
      (node (ref "RN3") (pin "2") (pinfunction "1_2") (pintype "passive"))
      (node (ref "T26") (pin "3") (pinfunction "D_3") (pintype "passive"))
    )
    (net (code "125") (name "Net-(RN3C-1)") (class "Default")
      (node (ref "RN3") (pin "3") (pinfunction "1_3") (pintype "passive"))
      (node (ref "T27") (pin "3") (pinfunction "D_3") (pintype "passive"))
    )
    (net (code "126") (name "Net-(RN3D-1)") (class "Default")
      (node (ref "RN3") (pin "4") (pinfunction "1_4") (pintype "passive"))
      (node (ref "T28") (pin "3") (pinfunction "D_3") (pintype "passive"))
    )
    (net (code "127") (name "Net-(RN4B-1)") (class "Default")
      (node (ref "RN4") (pin "2") (pinfunction "1_2") (pintype "passive"))
      (node (ref "T30") (pin "3") (pinfunction "D_3") (pintype "passive"))
    )
    (net (code "128") (name "Net-(RN4C-1)") (class "Default")
      (node (ref "RN4") (pin "3") (pinfunction "1_3") (pintype "passive"))
      (node (ref "T31") (pin "3") (pinfunction "D_3") (pintype "passive"))
    )
    (net (code "129") (name "Net-(RN4D-1)") (class "Default")
      (node (ref "RN4") (pin "4") (pinfunction "1_4") (pintype "passive"))
      (node (ref "T32") (pin "3") (pinfunction "D_3") (pintype "passive"))
    )
    (net (code "130") (name "Net-(RN9D-1)") (class "Default")
      (node (ref "C15") (pin "2") (pinfunction "2_2") (pintype "passive"))
      (node (ref "R9") (pin "2") (pinfunction "2_2") (pintype "passive"))
      (node (ref "RN9") (pin "4") (pinfunction "1_4") (pintype "passive"))
      (node (ref "SJ2") (pin "1") (pinfunction "1_1") (pintype "passive"))
      (node (ref "U2") (pin "P1") (pinfunction "OUT_P1") (pintype "output"))
    )
    (net (code "131") (name "Net-(RN9D-2)") (class "Default")
      (node (ref "R8") (pin "1") (pinfunction "1_1") (pintype "passive"))
      (node (ref "RN9") (pin "5") (pinfunction "2_5") (pintype "passive"))
      (node (ref "U2") (pin "P4") (pinfunction "IN-_P4") (pintype "input"))
    )
    (net (code "132") (name "Net-(S1-O)") (class "Default")
      (node (ref "JP7") (pin "1") (pinfunction "1_1") (pintype "passive"))
      (node (ref "S1") (pin "1") (pinfunction "O_1") (pintype "passive"))
    )
    (net (code "133") (name "Net-(S1-P)") (class "Default")
      (node (ref "BATT1") (pin "+") (pinfunction "+_+") (pintype "power_in"))
      (node (ref "S1") (pin "2") (pinfunction "P_2") (pintype "passive"))
    )
    (net (code "134") (name "Net-(T17-D)") (class "Default")
      (node (ref "RN1") (pin "1") (pinfunction "1_1") (pintype "passive"))
      (node (ref "T17") (pin "3") (pinfunction "D_3") (pintype "passive"))
    )
    (net (code "135") (name "Net-(T21-D)") (class "Default")
      (node (ref "RN2") (pin "1") (pinfunction "1_1") (pintype "passive"))
      (node (ref "T21") (pin "3") (pinfunction "D_3") (pintype "passive"))
    )
    (net (code "136") (name "Net-(T25-D)") (class "Default")
      (node (ref "RN3") (pin "1") (pinfunction "1_1") (pintype "passive"))
      (node (ref "T25") (pin "3") (pinfunction "D_3") (pintype "passive"))
    )
    (net (code "137") (name "Net-(T29-D)") (class "Default")
      (node (ref "RN4") (pin "1") (pinfunction "1_1") (pintype "passive"))
      (node (ref "T29") (pin "3") (pinfunction "D_3") (pintype "passive"))
    )
    (net (code "138") (name "Net-(U1-SW)") (class "Default")
      (node (ref "L1") (pin "1") (pinfunction "1_1") (pintype "passive"))
      (node (ref "U1") (pin "3") (pinfunction "SW_3") (pintype "passive"))
    )
    (net (code "139") (name "Net-(U2-IN+)") (class "Default")
      (node (ref "SJ3") (pin "2") (pinfunction "2_2") (pintype "passive"))
      (node (ref "U2") (pin "P3") (pinfunction "IN+_P3") (pintype "input"))
    )
    (net (code "140") (name "V-BATT_DIRECT") (class "Default")
      (node (ref "C1") (pin "1") (pinfunction "1_1") (pintype "passive"))
      (node (ref "C17") (pin "+") (pinfunction "+_+") (pintype "passive"))
      (node (ref "C18") (pin "+") (pinfunction "+_+") (pintype "passive"))
      (node (ref "D1") (pin "A") (pinfunction "A_A") (pintype "passive"))
      (node (ref "RN5") (pin "1") (pinfunction "1_1") (pintype "passive"))
      (node (ref "RN5") (pin "2") (pinfunction "1_2") (pintype "passive"))
      (node (ref "RN5") (pin "3") (pinfunction "1_3") (pintype "passive"))
      (node (ref "RN5") (pin "4") (pinfunction "1_4") (pintype "passive"))
      (node (ref "RN6") (pin "1") (pinfunction "1_1") (pintype "passive"))
      (node (ref "RN6") (pin "2") (pinfunction "1_2") (pintype "passive"))
      (node (ref "RN6") (pin "3") (pinfunction "1_3") (pintype "passive"))
      (node (ref "RN6") (pin "4") (pinfunction "1_4") (pintype "passive"))
      (node (ref "RN7") (pin "1") (pinfunction "1_1") (pintype "passive"))
      (node (ref "RN7") (pin "2") (pinfunction "1_2") (pintype "passive"))
      (node (ref "RN7") (pin "3") (pinfunction "1_3") (pintype "passive"))
      (node (ref "RN7") (pin "4") (pinfunction "1_4") (pintype "passive"))
      (node (ref "RN8") (pin "1") (pinfunction "1_1") (pintype "passive"))
      (node (ref "RN8") (pin "2") (pinfunction "1_2") (pintype "passive"))
      (node (ref "RN8") (pin "3") (pinfunction "1_3") (pintype "passive"))
      (node (ref "RN8") (pin "4") (pinfunction "1_4") (pintype "passive"))
      (node (ref "RN9") (pin "8") (pinfunction "2_8") (pintype "passive"))
      (node (ref "S1") (pin "3") (pinfunction "S_3") (pintype "passive"))
      (node (ref "SJ1") (pin "1") (pinfunction "1_1") (pintype "passive"))
      (node (ref "T1") (pin "2") (pinfunction "S_2") (pintype "passive"))
      (node (ref "T10") (pin "2") (pinfunction "S_2") (pintype "passive"))
      (node (ref "T11") (pin "2") (pinfunction "S_2") (pintype "passive"))
      (node (ref "T12") (pin "2") (pinfunction "S_2") (pintype "passive"))
      (node (ref "T13") (pin "2") (pinfunction "S_2") (pintype "passive"))
      (node (ref "T14") (pin "2") (pinfunction "S_2") (pintype "passive"))
      (node (ref "T15") (pin "2") (pinfunction "S_2") (pintype "passive"))
      (node (ref "T16") (pin "2") (pinfunction "S_2") (pintype "passive"))
      (node (ref "T2") (pin "2") (pinfunction "S_2") (pintype "passive"))
      (node (ref "T3") (pin "2") (pinfunction "S_2") (pintype "passive"))
      (node (ref "T4") (pin "2") (pinfunction "S_2") (pintype "passive"))
      (node (ref "T5") (pin "2") (pinfunction "S_2") (pintype "passive"))
      (node (ref "T6") (pin "2") (pinfunction "S_2") (pintype "passive"))
      (node (ref "T7") (pin "2") (pinfunction "S_2") (pintype "passive"))
      (node (ref "T8") (pin "2") (pinfunction "S_2") (pintype "passive"))
      (node (ref "T9") (pin "2") (pinfunction "S_2") (pintype "passive"))
      (node (ref "U1") (pin "1") (pinfunction "EN_1") (pintype "input"))
      (node (ref "U1") (pin "4") (pinfunction "VIN_4") (pintype "power_in"))
    )
    (net (code "141") (name "VCC") (class "Default")
      (node (ref "C11") (pin "1") (pinfunction "1_1") (pintype "passive"))
      (node (ref "C12") (pin "1") (pinfunction "1_1") (pintype "passive"))
      (node (ref "C16") (pin "1") (pinfunction "1_1") (pintype "passive"))
      (node (ref "C5") (pin "1") (pinfunction "1_1") (pintype "passive"))
      (node (ref "C6") (pin "1") (pinfunction "1_1") (pintype "passive"))
      (node (ref "C7") (pin "1") (pinfunction "1_1") (pintype "passive"))
      (node (ref "C8") (pin "1") (pinfunction "1_1") (pintype "passive"))
      (node (ref "IC1") (pin "23") (pinfunction "VCCIO1_23") (pintype "power_in"))
      (node (ref "IC1") (pin "39") (pinfunction "VCCIO2_39") (pintype "power_in"))
      (node (ref "IC1") (pin "57") (pinfunction "VCCIO2_57") (pintype "power_in"))
      (node (ref "IC1") (pin "6") (pinfunction "VCCIO1_6") (pintype "power_in"))
      (node (ref "IC2") (pin "4") (pinfunction "VCC_4") (pintype "power_in"))
      (node (ref "IC2") (pin "6") (pinfunction "VCC_6") (pintype "power_in"))
      (node (ref "JP1") (pin "P$4") (pinfunction "4_P$4") (pintype "bidirectional"))
      (node (ref "JP2") (pin "P$2") (pinfunction "2_P$2") (pintype "bidirectional"))
      (node (ref "JP3") (pin "2") (pinfunction "2_2") (pintype "passive"))
      (node (ref "JP4") (pin "3") (pinfunction "3_3") (pintype "passive"))
      (node (ref "JP5") (pin "3") (pinfunction "3_3") (pintype "passive"))
      (node (ref "JP6") (pin "1") (pinfunction "1_1") (pintype "passive"))
      (node (ref "L2") (pin "1") (pinfunction "1_1") (pintype "passive"))
      (node (ref "R10") (pin "2") (pinfunction "2_2") (pintype "passive"))
      (node (ref "R11") (pin "2") (pinfunction "2_2") (pintype "passive"))
      (node (ref "R2") (pin "2") (pinfunction "2_2") (pintype "passive"))
      (node (ref "R3") (pin "2") (pinfunction "2_2") (pintype "passive"))
      (node (ref "R4") (pin "2") (pinfunction "2_2") (pintype "passive"))
      (node (ref "SJ1") (pin "2") (pinfunction "2_2") (pintype "passive"))
    )
    (net (code "142") (name "unconnected-(IC1-IO27-Pad27)") (class "Default")
      (node (ref "IC1") (pin "27") (pinfunction "IO27_27") (pintype "bidirectional"))
    )
    (net (code "143") (name "unconnected-(IC1-IO30-Pad30)") (class "Default")
      (node (ref "IC1") (pin "30") (pinfunction "IO30_30") (pintype "bidirectional"))
    )
    (net (code "144") (name "unconnected-(IC1-IO31-Pad31)") (class "Default")
      (node (ref "IC1") (pin "31") (pinfunction "IO31_31") (pintype "bidirectional"))
    )
    (net (code "145") (name "unconnected-(IC1-IO32-Pad32)") (class "Default")
      (node (ref "IC1") (pin "32") (pinfunction "IO32_32") (pintype "bidirectional"))
    )
    (net (code "146") (name "unconnected-(IC1-IO33-Pad33)") (class "Default")
      (node (ref "IC1") (pin "33") (pinfunction "IO33_33") (pintype "bidirectional"))
    )
    (net (code "147") (name "unconnected-(IC1-IO42{slash}CLK3-Pad42)") (class "Default")
      (node (ref "IC1") (pin "42") (pinfunction "IO42/CLK3_42") (pintype "bidirectional"))
    )
    (net (code "148") (name "unconnected-(JP1-6-PadP$6)") (class "Default")
      (node (ref "JP1") (pin "P$6") (pinfunction "6_P$6") (pintype "bidirectional"))
    )
    (net (code "149") (name "unconnected-(JP1-7-PadP$7)") (class "Default")
      (node (ref "JP1") (pin "P$7") (pinfunction "7_P$7") (pintype "bidirectional"))
    )
    (net (code "150") (name "unconnected-(JP1-8-PadP$8)") (class "Default")
      (node (ref "JP1") (pin "P$8") (pinfunction "8_P$8") (pintype "bidirectional"))
    )
  )
)
